# MCU.net
KiCad netlist of a schematic drawn in Altium Designer
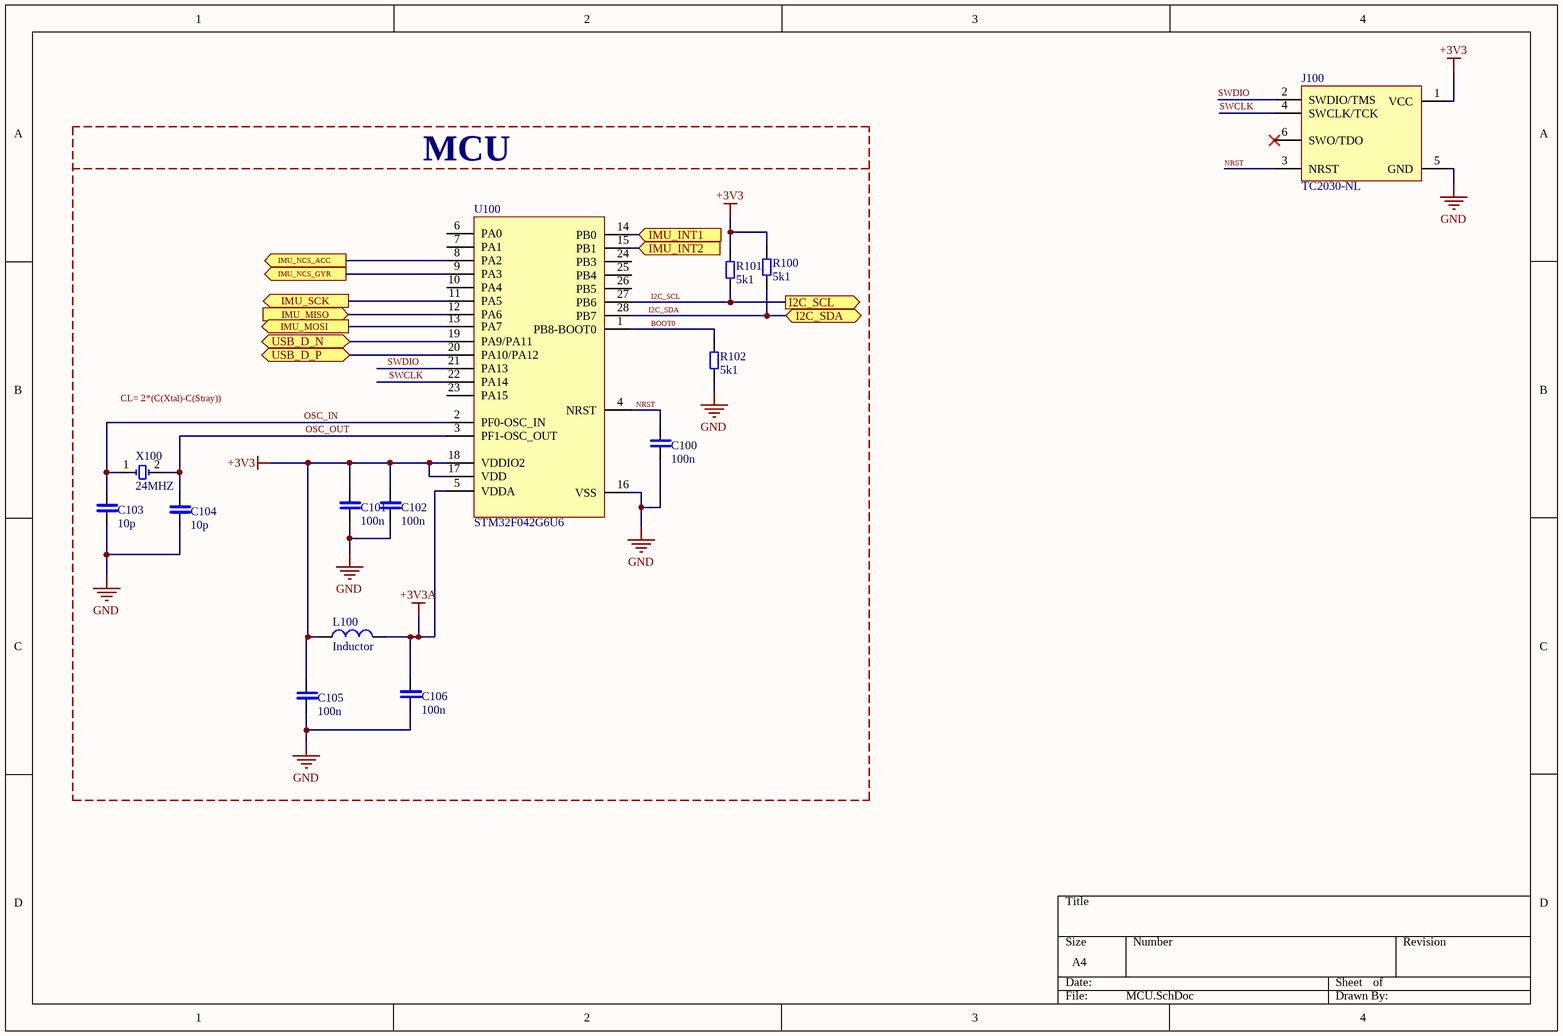
[diagram p0: MCU.SchDoc]

(export (version "E")
  (design (tool "Eeschema 10.0.6"))
  (components
    (comp (ref "C100")
      (value "100n")
      (footprint "CAP-0805-NP0")
      (description "Surface Mount Ceramic Multilayer Capacitor 27pF 1% C0G 50V 0805 Paper T/R")
      (fields
        (field (name "MANUFACTURER") "Yageo")
        (field (name "MANUFACTURER PART NUMBER") "CC0805FRNPO9BN270")
      )
      (libsource (lib "Schlib2") (part "CAP-0805-NP0-27pF"))
    )
    (comp (ref "C101")
      (value "100n")
      (footprint "CAP-0805-NP0")
      (description "Surface Mount Ceramic Multilayer Capacitor 27pF 1% C0G 50V 0805 Paper T/R")
      (fields
        (field (name "MANUFACTURER") "Yageo")
        (field (name "MANUFACTURER PART NUMBER") "CC0805FRNPO9BN270")
      )
      (libsource (lib "Schlib2") (part "CAP-0805-NP0-27pF"))
    )
    (comp (ref "C102")
      (value "100n")
      (footprint "CAP-0805-NP0")
      (description "Surface Mount Ceramic Multilayer Capacitor 27pF 1% C0G 50V 0805 Paper T/R")
      (fields
        (field (name "MANUFACTURER") "Yageo")
        (field (name "MANUFACTURER PART NUMBER") "CC0805FRNPO9BN270")
      )
      (libsource (lib "Schlib2") (part "CAP-0805-NP0-27pF"))
    )
    (comp (ref "C103")
      (value "10p")
      (footprint "CAP-0805-NP0")
      (description "Surface Mount Ceramic Multilayer Capacitor 27pF 1% C0G 50V 0805 Paper T/R")
      (fields
        (field (name "MANUFACTURER") "Yageo")
        (field (name "MANUFACTURER PART NUMBER") "CC0805FRNPO9BN270")
      )
      (libsource (lib "Schlib2") (part "CAP-0805-NP0-27pF"))
    )
    (comp (ref "C104")
      (value "10p")
      (footprint "CAP-0805-NP0")
      (description "Surface Mount Ceramic Multilayer Capacitor 27pF 1% C0G 50V 0805 Paper T/R")
      (fields
        (field (name "MANUFACTURER") "Yageo")
        (field (name "MANUFACTURER PART NUMBER") "CC0805FRNPO9BN270")
      )
      (libsource (lib "Schlib2") (part "CAP-0805-NP0-27pF"))
    )
    (comp (ref "C105")
      (value "100n")
      (footprint "CAP-0805-NP0")
      (description "Surface Mount Ceramic Multilayer Capacitor 27pF 1% C0G 50V 0805 Paper T/R")
      (fields
        (field (name "MANUFACTURER") "Yageo")
        (field (name "MANUFACTURER PART NUMBER") "CC0805FRNPO9BN270")
      )
      (libsource (lib "Schlib2") (part "CAP-0805-NP0-27pF"))
    )
    (comp (ref "C106")
      (value "100n")
      (footprint "CAP-0805-NP0")
      (description "Surface Mount Ceramic Multilayer Capacitor 27pF 1% C0G 50V 0805 Paper T/R")
      (fields
        (field (name "MANUFACTURER") "Yageo")
        (field (name "MANUFACTURER PART NUMBER") "CC0805FRNPO9BN270")
      )
      (libsource (lib "Schlib2") (part "CAP-0805-NP0-27pF"))
    )
    (comp (ref "J100")
      (value "TC2030-NL")
      (footprint "TC2030-NL-FP")
      (libsource (lib "Schematic-Lib-Zhrzkn") (part "TC2030-NL"))
    )
    (comp (ref "L100")
      (value "Inductor")
      (footprint "IND_0603")
      (libsource (lib "Schematic-Lib-Zhrzkn") (part "Inductor"))
    )
    (comp (ref "R100")
      (value "5k1")
      (footprint "RES-0603")
      (description "贴片电阻 1000Ω ± 1.00% 0.1W ± 100ppm/℃ 0603")
      (fields
        (field (name "MANUFACTURER") "Vishay Dale")
        (field (name "MANUFACTURER PART NUMBER") "CRCW06031K00FKEA")
      )
      (libsource (lib "Schlib2") (part "RES-0603-1k"))
    )
    (comp (ref "R101")
      (value "5k1")
      (footprint "RES-0603")
      (description "贴片电阻 1000Ω ± 1.00% 0.1W ± 100ppm/℃ 0603")
      (fields
        (field (name "MANUFACTURER") "Vishay Dale")
        (field (name "MANUFACTURER PART NUMBER") "CRCW06031K00FKEA")
      )
      (libsource (lib "Schlib2") (part "RES-0603-1k"))
    )
    (comp (ref "R102")
      (value "5k1")
      (footprint "RES-0603")
      (description "贴片电阻 1000Ω ± 1.00% 0.1W ± 100ppm/℃ 0603")
      (fields
        (field (name "MANUFACTURER") "Vishay Dale")
        (field (name "MANUFACTURER PART NUMBER") "CRCW06031K00FKEA")
      )
      (libsource (lib "Schlib2") (part "RES-0603-1k"))
    )
    (comp (ref "U100")
      (value "STM32F042G6U6")
      (footprint "STM32F042G6U6")
      (description "MCU 32-Bit STM32F ARM Cortex M0 RISC 32KB Flash 2.5V/3.3V 28-Pin UFQFPN Tray")
      (fields (field (name "MANUFACTURER") "STMicroelectronics"))
      (libsource (lib "Schematic-Lib-Zhrzkn") (part "STM32F042G6U6"))
    )
    (comp (ref "X100")
      (value "24MHZ")
      (footprint "ABM7-8MHZ")
      (description "Crystal 8MHz ±20ppm (Tol) ±30ppm (Stability) 18pF FUND 100Ohm 2-Pin Mini-CSMD T/R")
      (fields
        (field (name "MANUFACTURER") "Abracon")
        (field (name "MANUFACTURER PART NUMBER") "ABM7-8.000MHZ-D2Y-T")
      )
      (libsource (lib "Schlib2") (part "ABM7-8MHZ"))
    )
  )
  (nets
    (net (code "1") (name "+3V3") (class "Default")
      (node (ref "C101") (pin "1") (pinfunction "1_1") (pintype "passive"))
      (node (ref "C102") (pin "1") (pinfunction "1_1") (pintype "passive"))
      (node (ref "C105") (pin "1") (pinfunction "1_1") (pintype "passive"))
      (node (ref "J100") (pin "1") (pinfunction "VCC_1") (pintype "passive"))
      (node (ref "L100") (pin "1") (pinfunction "1_1") (pintype "passive"))
      (node (ref "R100") (pin "2") (pinfunction "2_2") (pintype "passive"))
      (node (ref "R101") (pin "2") (pinfunction "2_2") (pintype "passive"))
      (node (ref "U100") (pin "17") (pinfunction "VDD_17") (pintype "passive"))
      (node (ref "U100") (pin "18") (pinfunction "VDDIO2_18") (pintype "passive"))
    )
    (net (code "2") (name "+3V3A") (class "Default")
      (node (ref "C106") (pin "1") (pinfunction "1_1") (pintype "passive"))
      (node (ref "L100") (pin "2") (pinfunction "2_2") (pintype "passive"))
      (node (ref "U100") (pin "5") (pinfunction "VDDA_5") (pintype "passive"))
    )
    (net (code "3") (name "/BOOT0") (class "Default")
      (node (ref "R102") (pin "2") (pinfunction "2_2") (pintype "passive"))
      (node (ref "U100") (pin "1") (pinfunction "PB8-BOOT0_1") (pintype "passive"))
    )
    (net (code "4") (name "/I2C_SCL") (class "Default")
      (node (ref "R101") (pin "1") (pinfunction "1_1") (pintype "passive"))
      (node (ref "U100") (pin "27") (pinfunction "PB6_27") (pintype "passive"))
    )
    (net (code "5") (name "/I2C_SDA") (class "Default")
      (node (ref "R100") (pin "1") (pinfunction "1_1") (pintype "passive"))
      (node (ref "U100") (pin "28") (pinfunction "PB7_28") (pintype "passive"))
    )
    (net (code "6") (name "/IMU_INT1") (class "Default")
      (node (ref "U100") (pin "14") (pinfunction "PB0_14") (pintype "passive"))
    )
    (net (code "7") (name "/IMU_INT2") (class "Default")
      (node (ref "U100") (pin "15") (pinfunction "PB1_15") (pintype "passive"))
    )
    (net (code "8") (name "/IMU_MISO") (class "Default")
      (node (ref "U100") (pin "12") (pinfunction "PA6_12") (pintype "passive"))
    )
    (net (code "9") (name "/IMU_MOSI") (class "Default")
      (node (ref "U100") (pin "13") (pinfunction "PA7_13") (pintype "passive"))
    )
    (net (code "10") (name "/IMU_NCS_ACC") (class "Default")
      (node (ref "U100") (pin "8") (pinfunction "PA2_8") (pintype "passive"))
    )
    (net (code "11") (name "/IMU_NCS_GYR") (class "Default")
      (node (ref "U100") (pin "9") (pinfunction "PA3_9") (pintype "passive"))
    )
    (net (code "12") (name "/IMU_SCK") (class "Default")
      (node (ref "U100") (pin "11") (pinfunction "PA5_11") (pintype "passive"))
    )
    (net (code "13") (name "/NRST") (class "Default")
      (node (ref "C100") (pin "1") (pinfunction "1_1") (pintype "passive"))
      (node (ref "J100") (pin "3") (pinfunction "NRST_3") (pintype "passive"))
      (node (ref "U100") (pin "4") (pinfunction "NRST_4") (pintype "passive"))
    )
    (net (code "14") (name "/OSC_IN") (class "Default")
      (node (ref "C103") (pin "1") (pinfunction "1_1") (pintype "passive"))
      (node (ref "U100") (pin "2") (pinfunction "PF0-OSC_IN_2") (pintype "passive"))
      (node (ref "X100") (pin "1") (pintype "passive"))
    )
    (net (code "15") (name "/OSC_OUT") (class "Default")
      (node (ref "C104") (pin "1") (pinfunction "1_1") (pintype "passive"))
      (node (ref "U100") (pin "3") (pinfunction "PF1-OSC_OUT_3") (pintype "passive"))
      (node (ref "X100") (pin "2") (pintype "passive"))
    )
    (net (code "16") (name "/SWCLK") (class "Default")
      (node (ref "J100") (pin "4") (pinfunction "SWCLK/TCK_4") (pintype "passive"))
      (node (ref "U100") (pin "22") (pinfunction "PA14_22") (pintype "passive"))
    )
    (net (code "17") (name "/SWDIO") (class "Default")
      (node (ref "J100") (pin "2") (pinfunction "SWDIO/TMS_2") (pintype "passive"))
      (node (ref "U100") (pin "21") (pinfunction "PA13_21") (pintype "passive"))
    )
    (net (code "18") (name "/USB_D_N") (class "Default")
      (node (ref "U100") (pin "19") (pinfunction "PA9/PA11_19") (pintype "passive"))
    )
    (net (code "19") (name "/USB_D_P") (class "Default")
      (node (ref "U100") (pin "20") (pinfunction "PA10/PA12_20") (pintype "passive"))
    )
    (net (code "20") (name "GND") (class "Default")
      (node (ref "C100") (pin "2") (pinfunction "2_2") (pintype "passive"))
      (node (ref "C101") (pin "2") (pinfunction "2_2") (pintype "passive"))
      (node (ref "C102") (pin "2") (pinfunction "2_2") (pintype "passive"))
      (node (ref "C103") (pin "2") (pinfunction "2_2") (pintype "passive"))
      (node (ref "C104") (pin "2") (pinfunction "2_2") (pintype "passive"))
      (node (ref "C105") (pin "2") (pinfunction "2_2") (pintype "passive"))
      (node (ref "C106") (pin "2") (pinfunction "2_2") (pintype "passive"))
      (node (ref "J100") (pin "5") (pinfunction "GND_5") (pintype "passive"))
      (node (ref "R102") (pin "1") (pinfunction "1_1") (pintype "passive"))
      (node (ref "U100") (pin "16") (pinfunction "VSS_16") (pintype "passive"))
    )
    (net (code "21") (name "unconnected-(J100-SWO{slash}TDO-Pad6)") (class "Default")
      (node (ref "J100") (pin "6") (pinfunction "SWO/TDO_6") (pintype "passive+no_connect"))
    )
    (net (code "22") (name "unconnected-(U100-PA0-Pad6)") (class "Default")
      (node (ref "U100") (pin "6") (pinfunction "PA0_6") (pintype "passive"))
    )
    (net (code "23") (name "unconnected-(U100-PA1-Pad7)") (class "Default")
      (node (ref "U100") (pin "7") (pinfunction "PA1_7") (pintype "passive"))
    )
    (net (code "24") (name "unconnected-(U100-PA4-Pad10)") (class "Default")
      (node (ref "U100") (pin "10") (pinfunction "PA4_10") (pintype "passive"))
    )
    (net (code "25") (name "unconnected-(U100-PA15-Pad23)") (class "Default")
      (node (ref "U100") (pin "23") (pinfunction "PA15_23") (pintype "passive"))
    )
    (net (code "26") (name "unconnected-(U100-PB3-Pad24)") (class "Default")
      (node (ref "U100") (pin "24") (pinfunction "PB3_24") (pintype "passive"))
    )
    (net (code "27") (name "unconnected-(U100-PB4-Pad25)") (class "Default")
      (node (ref "U100") (pin "25") (pinfunction "PB4_25") (pintype "passive"))
    )
    (net (code "28") (name "unconnected-(U100-PB5-Pad26)") (class "Default")
      (node (ref "U100") (pin "26") (pinfunction "PB5_26") (pintype "passive"))
    )
  )
)
